# LMP2011basedV2.net
KiCad netlist of a schematic drawn in EAGLE
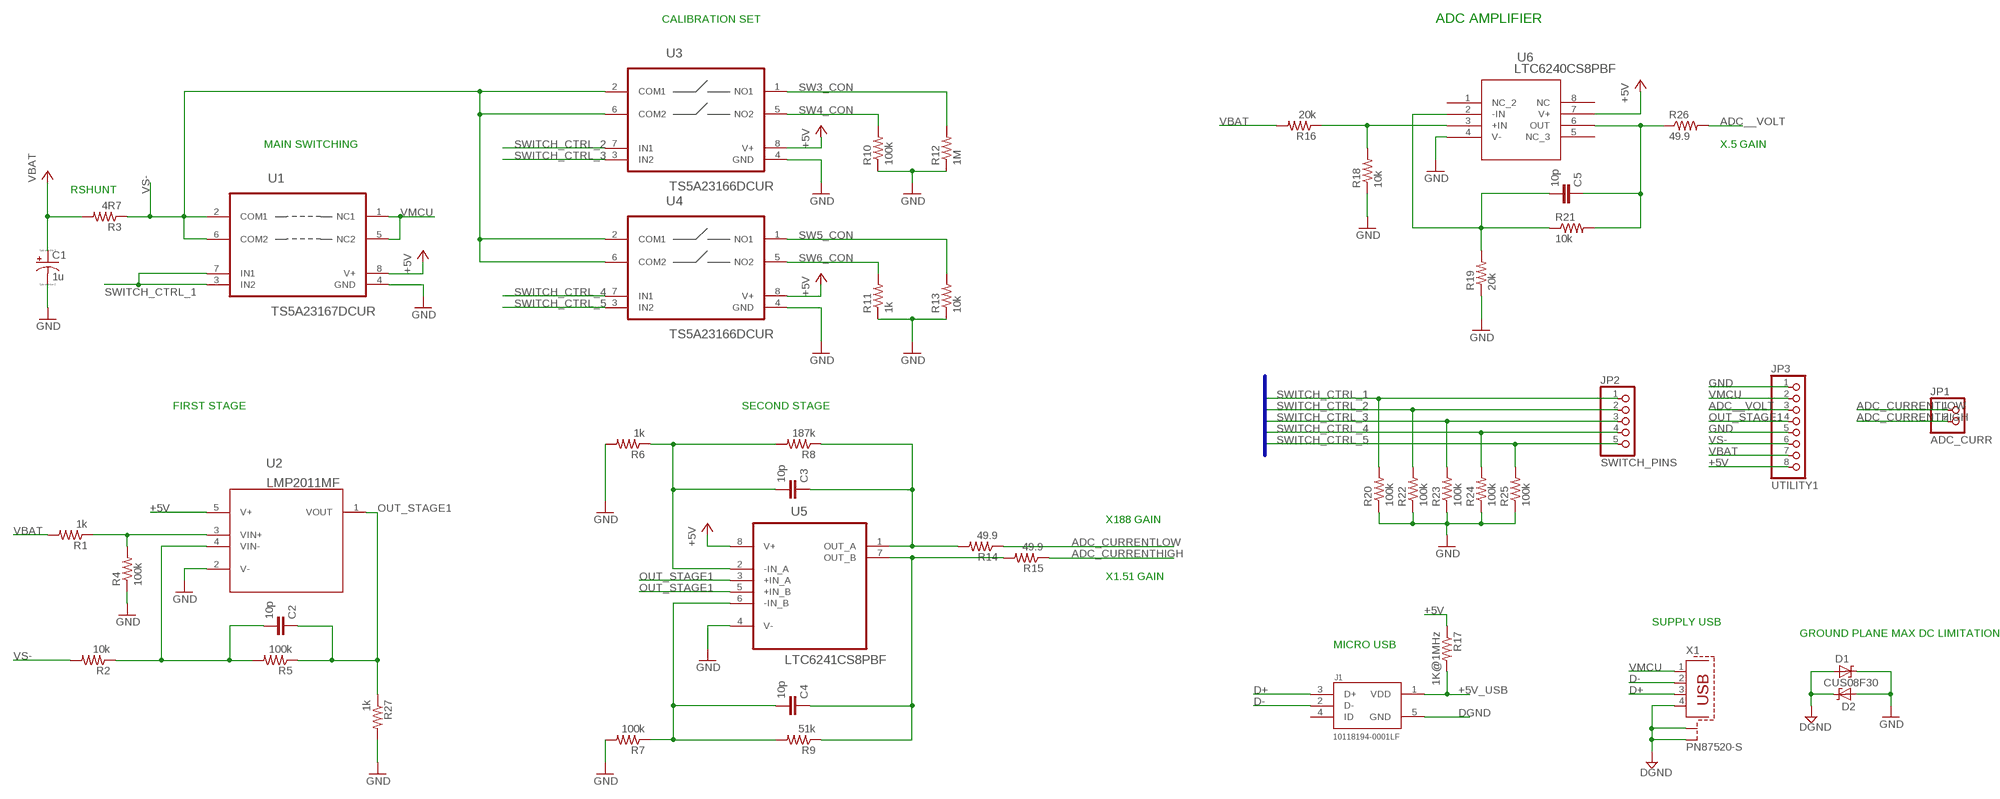
[diagram p0: schematic, sheet 1]

(export (version "E")
  (design (tool "Eeschema 10.0.6"))
  (components
    (comp (ref "C1")
      (value "1u")
      (footprint "eagle-import:PANASONIC_B")
      (libsource (lib "eagle-import") (part "CPOL-USB"))
    )
    (comp (ref "C2")
      (value "10p")
      (footprint "eagle-import:C0805")
      (libsource (lib "eagle-import") (part "C-EUC0805"))
    )
    (comp (ref "C3")
      (value "10p")
      (footprint "eagle-import:C0805")
      (libsource (lib "eagle-import") (part "C-EUC0805"))
    )
    (comp (ref "C4")
      (value "10p")
      (footprint "eagle-import:C0805")
      (libsource (lib "eagle-import") (part "C-EUC0805"))
    )
    (comp (ref "C5")
      (value "10p")
      (footprint "eagle-import:C0805")
      (libsource (lib "eagle-import") (part "C-EUC0805"))
    )
    (comp (ref "D1")
      (value "CUS08F30")
      (footprint "eagle-import:SOD323")
      (fields (field (name "MF") "TOSHIBA"))
      (libsource (lib "eagle-import") (part "CUS08F30"))
    )
    (comp (ref "D2")
      (value "CUS08F30")
      (footprint "eagle-import:SOD323")
      (fields (field (name "MF") "TOSHIBA"))
      (libsource (lib "eagle-import") (part "CUS08F30"))
    )
    (comp (ref "J1")
      (value "10118194-0001LF")
      (footprint "eagle-import:FRAMATOME_10118194-0001LF")
      (fields (field (name "MF") "Amphenol"))
      (libsource (lib "eagle-import") (part "10118194-0001LF"))
    )
    (comp (ref "JP1")
      (value "ADC_CURR")
      (footprint "eagle-import:1X02")
      (libsource (lib "eagle-import") (part "PINHD-1X2"))
    )
    (comp (ref "JP2")
      (value "SWITCH_PINS")
      (footprint "eagle-import:1X05")
      (libsource (lib "eagle-import") (part "PINHD-1X5"))
    )
    (comp (ref "JP3")
      (value "UTILITY1")
      (footprint "eagle-import:1X08")
      (libsource (lib "eagle-import") (part "PINHD-1X8"))
    )
    (comp (ref "R1")
      (value "1k")
      (footprint "eagle-import:R0805")
      (libsource (lib "eagle-import") (part "R-US_R0805"))
    )
    (comp (ref "R2")
      (value "10k")
      (footprint "eagle-import:R0805")
      (libsource (lib "eagle-import") (part "R-US_R0805"))
    )
    (comp (ref "R3")
      (value "4R7")
      (footprint "eagle-import:R0805")
      (libsource (lib "eagle-import") (part "R-US_R0805"))
    )
    (comp (ref "R4")
      (value "100k")
      (footprint "eagle-import:R0805")
      (libsource (lib "eagle-import") (part "R-US_R0805"))
    )
    (comp (ref "R5")
      (value "100k")
      (footprint "eagle-import:R0805")
      (libsource (lib "eagle-import") (part "R-US_R0805"))
    )
    (comp (ref "R6")
      (value "1k")
      (footprint "eagle-import:R0805")
      (libsource (lib "eagle-import") (part "R-US_R0805"))
    )
    (comp (ref "R7")
      (value "100k")
      (footprint "eagle-import:R0805")
      (libsource (lib "eagle-import") (part "R-US_R0805"))
    )
    (comp (ref "R8")
      (value "187k")
      (footprint "eagle-import:R0805")
      (libsource (lib "eagle-import") (part "R-US_R0805"))
    )
    (comp (ref "R9")
      (value "51k")
      (footprint "eagle-import:R0805")
      (libsource (lib "eagle-import") (part "R-US_R0805"))
    )
    (comp (ref "R10")
      (value "100k")
      (footprint "eagle-import:R0805")
      (libsource (lib "eagle-import") (part "R-US_R0805"))
    )
    (comp (ref "R11")
      (value "1k")
      (footprint "eagle-import:R0805")
      (libsource (lib "eagle-import") (part "R-US_R0805"))
    )
    (comp (ref "R12")
      (value "1M")
      (footprint "eagle-import:R0805")
      (libsource (lib "eagle-import") (part "R-US_R0805"))
    )
    (comp (ref "R13")
      (value "10k")
      (footprint "eagle-import:R0805")
      (libsource (lib "eagle-import") (part "R-US_R0805"))
    )
    (comp (ref "R14")
      (value "49.9")
      (footprint "eagle-import:R0805")
      (libsource (lib "eagle-import") (part "R-US_R0805"))
    )
    (comp (ref "R15")
      (value "49.9")
      (footprint "eagle-import:R0805")
      (libsource (lib "eagle-import") (part "R-US_R0805"))
    )
    (comp (ref "R16")
      (value "20k")
      (footprint "eagle-import:R0805")
      (libsource (lib "eagle-import") (part "R-US_R0805"))
    )
    (comp (ref "R17")
      (value "1K@1MHz")
      (footprint "eagle-import:R0805")
      (libsource (lib "eagle-import") (part "R-US_R0805"))
    )
    (comp (ref "R18")
      (value "10k")
      (footprint "eagle-import:R0805")
      (libsource (lib "eagle-import") (part "R-US_R0805"))
    )
    (comp (ref "R19")
      (value "20k")
      (footprint "eagle-import:R0805")
      (libsource (lib "eagle-import") (part "R-US_R0805"))
    )
    (comp (ref "R20")
      (value "100k")
      (footprint "eagle-import:R0805")
      (libsource (lib "eagle-import") (part "R-US_R0805"))
    )
    (comp (ref "R21")
      (value "10k")
      (footprint "eagle-import:R0805")
      (libsource (lib "eagle-import") (part "R-US_R0805"))
    )
    (comp (ref "R22")
      (value "100k")
      (footprint "eagle-import:R0805")
      (libsource (lib "eagle-import") (part "R-US_R0805"))
    )
    (comp (ref "R23")
      (value "100k")
      (footprint "eagle-import:R0805")
      (libsource (lib "eagle-import") (part "R-US_R0805"))
    )
    (comp (ref "R24")
      (value "100k")
      (footprint "eagle-import:R0805")
      (libsource (lib "eagle-import") (part "R-US_R0805"))
    )
    (comp (ref "R25")
      (value "100k")
      (footprint "eagle-import:R0805")
      (libsource (lib "eagle-import") (part "R-US_R0805"))
    )
    (comp (ref "R26")
      (value "49.9")
      (footprint "eagle-import:R0603")
      (libsource (lib "eagle-import") (part "R-US_R0603"))
    )
    (comp (ref "R27")
      (value "1k")
      (footprint "eagle-import:R0805")
      (libsource (lib "eagle-import") (part "R-US_R0805"))
    )
    (comp (ref "U1")
      (value "TS5A23167DCUR")
      (footprint "eagle-import:SOP50P310X90-8N")
      (fields (field (name "MF") "Texas Instruments"))
      (libsource (lib "eagle-import") (part "TS5A23167DCUR"))
    )
    (comp (ref "U2")
      (value "LMP2011MF")
      (footprint "eagle-import:SOT95P285X120-5N")
      (fields
        (field (name "DIGI-KEY_PART_NUMBER") "LMP2011MF/NOPBCT-ND")
        (field (name "MF") "Texas Instruments")
        (field (name "MP") "LMP2011MF/NOPB")
      )
      (libsource (lib "eagle-import") (part "LMP2011MF"))
    )
    (comp (ref "U3")
      (value "TS5A23166DCUR")
      (footprint "eagle-import:SOP50P310X90-8N")
      (fields (field (name "MF") "Texas Instruments"))
      (libsource (lib "eagle-import") (part "TS5A23166DCUR"))
    )
    (comp (ref "U4")
      (value "TS5A23166DCUR")
      (footprint "eagle-import:SOP50P310X90-8N")
      (fields (field (name "MF") "Texas Instruments"))
      (libsource (lib "eagle-import") (part "TS5A23166DCUR"))
    )
    (comp (ref "U5")
      (value "LTC6241CS8PBF")
      (footprint "eagle-import:SOIC127P600X175-8N")
      (fields (field (name "MF") "Linear Technology") (field (name "MP") "LTC6241CS8#PBF"))
      (libsource (lib "eagle-import") (part "LTC6241CS8PBF"))
    )
    (comp (ref "U6")
      (value "LTC6240CS8PBF")
      (footprint "eagle-import:SO-8_S")
      (fields (field (name "MF") "Linear Technology") (field (name "MP") "LTC6240CS8#PBF"))
      (libsource (lib "eagle-import") (part "LTC6240CS8PBF"))
    )
    (comp (ref "X1")
      (value "PN87520-S")
      (footprint "eagle-import:PN87520-S")
      (libsource (lib "eagle-import") (part "PN87520-S"))
    )
  )
  (nets
    (net (code "1") (name "+5V") (class "Default")
      (node (ref "JP3") (pin "8") (pinfunction "8_8") (pintype "passive"))
      (node (ref "R17") (pin "1") (pinfunction "1_1") (pintype "passive"))
      (node (ref "U1") (pin "8") (pinfunction "V+_8") (pintype "power_in"))
      (node (ref "U2") (pin "5") (pinfunction "V+_5") (pintype "power_in"))
      (node (ref "U3") (pin "8") (pinfunction "V+_8") (pintype "power_in"))
      (node (ref "U4") (pin "8") (pinfunction "V+_8") (pintype "power_in"))
      (node (ref "U5") (pin "8") (pinfunction "V+_8") (pintype "power_in"))
      (node (ref "U6") (pin "7") (pinfunction "V+_7") (pintype "power_in"))
    )
    (net (code "2") (name "/+5V_USB") (class "Default")
      (node (ref "J1") (pin "1") (pinfunction "VDD_1") (pintype "power_in"))
      (node (ref "R17") (pin "2") (pinfunction "2_2") (pintype "passive"))
    )
    (net (code "3") (name "/ADC_CURRENTHIGH") (class "Default")
      (node (ref "JP1") (pin "2") (pinfunction "2_2") (pintype "passive"))
      (node (ref "R15") (pin "1") (pinfunction "1_1") (pintype "passive"))
    )
    (net (code "4") (name "/ADC_CURRENTLOW") (class "Default")
      (node (ref "JP1") (pin "1") (pinfunction "1_1") (pintype "passive"))
      (node (ref "R14") (pin "1") (pinfunction "1_1") (pintype "passive"))
    )
    (net (code "5") (name "/ADC__VOLT") (class "Default")
      (node (ref "JP3") (pin "3") (pinfunction "3_3") (pintype "passive"))
      (node (ref "R26") (pin "2") (pinfunction "2_2") (pintype "passive"))
    )
    (net (code "6") (name "/D+") (class "Default")
      (node (ref "J1") (pin "3") (pinfunction "D+_3") (pintype "bidirectional"))
      (node (ref "X1") (pin "3") (pinfunction "3_3") (pintype "passive"))
    )
    (net (code "7") (name "/D-") (class "Default")
      (node (ref "J1") (pin "2") (pinfunction "D-_2") (pintype "bidirectional"))
      (node (ref "X1") (pin "2") (pinfunction "2_2") (pintype "passive"))
    )
    (net (code "8") (name "/OUT_STAGE1") (class "Default")
      (node (ref "C2") (pin "1") (pinfunction "1_1") (pintype "passive"))
      (node (ref "JP3") (pin "4") (pinfunction "4_4") (pintype "passive"))
      (node (ref "R27") (pin "1") (pinfunction "1_1") (pintype "passive"))
      (node (ref "R5") (pin "1") (pinfunction "1_1") (pintype "passive"))
      (node (ref "U2") (pin "1") (pinfunction "VOUT_1") (pintype "output"))
      (node (ref "U5") (pin "3") (pinfunction "+IN_A_3") (pintype "input"))
      (node (ref "U5") (pin "5") (pinfunction "+IN_B_5") (pintype "input"))
    )
    (net (code "9") (name "/SW3_CON") (class "Default")
      (node (ref "R12") (pin "2") (pinfunction "2_2") (pintype "passive"))
      (node (ref "U3") (pin "1") (pinfunction "NO1_1") (pintype "bidirectional"))
    )
    (net (code "10") (name "/SW4_CON") (class "Default")
      (node (ref "R10") (pin "2") (pinfunction "2_2") (pintype "passive"))
      (node (ref "U3") (pin "5") (pinfunction "NO2_5") (pintype "bidirectional"))
    )
    (net (code "11") (name "/SW5_CON") (class "Default")
      (node (ref "R13") (pin "2") (pinfunction "2_2") (pintype "passive"))
      (node (ref "U4") (pin "1") (pinfunction "NO1_1") (pintype "bidirectional"))
    )
    (net (code "12") (name "/SW6_CON") (class "Default")
      (node (ref "R11") (pin "2") (pinfunction "2_2") (pintype "passive"))
      (node (ref "U4") (pin "5") (pinfunction "NO2_5") (pintype "bidirectional"))
    )
    (net (code "13") (name "/SWITCH_CTRL_1") (class "Default")
      (node (ref "JP2") (pin "1") (pinfunction "1_1") (pintype "passive"))
      (node (ref "R20") (pin "2") (pinfunction "2_2") (pintype "passive"))
      (node (ref "U1") (pin "3") (pinfunction "IN2_3") (pintype "input"))
      (node (ref "U1") (pin "7") (pinfunction "IN1_7") (pintype "input"))
    )
    (net (code "14") (name "/SWITCH_CTRL_2") (class "Default")
      (node (ref "JP2") (pin "2") (pinfunction "2_2") (pintype "passive"))
      (node (ref "R22") (pin "2") (pinfunction "2_2") (pintype "passive"))
      (node (ref "U3") (pin "7") (pinfunction "IN1_7") (pintype "input"))
    )
    (net (code "15") (name "/SWITCH_CTRL_3") (class "Default")
      (node (ref "JP2") (pin "3") (pinfunction "3_3") (pintype "passive"))
      (node (ref "R23") (pin "2") (pinfunction "2_2") (pintype "passive"))
      (node (ref "U3") (pin "3") (pinfunction "IN2_3") (pintype "input"))
    )
    (net (code "16") (name "/SWITCH_CTRL_4") (class "Default")
      (node (ref "JP2") (pin "4") (pinfunction "4_4") (pintype "passive"))
      (node (ref "R24") (pin "2") (pinfunction "2_2") (pintype "passive"))
      (node (ref "U4") (pin "7") (pinfunction "IN1_7") (pintype "input"))
    )
    (net (code "17") (name "/SWITCH_CTRL_5") (class "Default")
      (node (ref "JP2") (pin "5") (pinfunction "5_5") (pintype "passive"))
      (node (ref "R25") (pin "2") (pinfunction "2_2") (pintype "passive"))
      (node (ref "U4") (pin "3") (pinfunction "IN2_3") (pintype "input"))
    )
    (net (code "18") (name "/VMCU") (class "Default")
      (node (ref "JP3") (pin "2") (pinfunction "2_2") (pintype "passive"))
      (node (ref "U1") (pin "1") (pinfunction "NC1_1") (pintype "bidirectional"))
      (node (ref "U1") (pin "5") (pinfunction "NC2_5") (pintype "bidirectional"))
      (node (ref "X1") (pin "1") (pinfunction "1_1") (pintype "passive"))
    )
    (net (code "19") (name "/VS-") (class "Default")
      (node (ref "JP3") (pin "6") (pinfunction "6_6") (pintype "passive"))
      (node (ref "R2") (pin "2") (pinfunction "2_2") (pintype "passive"))
      (node (ref "R3") (pin "1") (pinfunction "1_1") (pintype "passive"))
      (node (ref "U1") (pin "2") (pinfunction "COM1_2") (pintype "bidirectional"))
      (node (ref "U1") (pin "6") (pinfunction "COM2_6") (pintype "bidirectional"))
      (node (ref "U3") (pin "2") (pinfunction "COM1_2") (pintype "bidirectional"))
      (node (ref "U3") (pin "6") (pinfunction "COM2_6") (pintype "bidirectional"))
      (node (ref "U4") (pin "2") (pinfunction "COM1_2") (pintype "bidirectional"))
      (node (ref "U4") (pin "6") (pinfunction "COM2_6") (pintype "bidirectional"))
    )
    (net (code "20") (name "DGND") (class "Default")
      (node (ref "D1") (pin "A") (pinfunction "A_A") (pintype "passive"))
      (node (ref "D2") (pin "C") (pinfunction "C_C") (pintype "passive"))
      (node (ref "J1") (pin "5") (pinfunction "GND_5") (pintype "power_in"))
      (node (ref "X1") (pin "4") (pinfunction "4_4") (pintype "passive"))
      (node (ref "X1") (pin "S1") (pinfunction "S1_S1") (pintype "passive"))
      (node (ref "X1") (pin "S2") (pinfunction "S2_S2") (pintype "passive"))
    )
    (net (code "21") (name "GND") (class "Default")
      (node (ref "C1") (pin "-") (pinfunction "-_-") (pintype "passive"))
      (node (ref "D1") (pin "C") (pinfunction "C_C") (pintype "passive"))
      (node (ref "D2") (pin "A") (pinfunction "A_A") (pintype "passive"))
      (node (ref "JP3") (pin "1") (pinfunction "1_1") (pintype "passive"))
      (node (ref "JP3") (pin "5") (pinfunction "5_5") (pintype "passive"))
      (node (ref "R10") (pin "1") (pinfunction "1_1") (pintype "passive"))
      (node (ref "R11") (pin "1") (pinfunction "1_1") (pintype "passive"))
      (node (ref "R12") (pin "1") (pinfunction "1_1") (pintype "passive"))
      (node (ref "R13") (pin "1") (pinfunction "1_1") (pintype "passive"))
      (node (ref "R18") (pin "1") (pinfunction "1_1") (pintype "passive"))
      (node (ref "R19") (pin "1") (pinfunction "1_1") (pintype "passive"))
      (node (ref "R20") (pin "1") (pinfunction "1_1") (pintype "passive"))
      (node (ref "R22") (pin "1") (pinfunction "1_1") (pintype "passive"))
      (node (ref "R23") (pin "1") (pinfunction "1_1") (pintype "passive"))
      (node (ref "R24") (pin "1") (pinfunction "1_1") (pintype "passive"))
      (node (ref "R25") (pin "1") (pinfunction "1_1") (pintype "passive"))
      (node (ref "R27") (pin "2") (pinfunction "2_2") (pintype "passive"))
      (node (ref "R4") (pin "1") (pinfunction "1_1") (pintype "passive"))
      (node (ref "R6") (pin "2") (pinfunction "2_2") (pintype "passive"))
      (node (ref "R7") (pin "2") (pinfunction "2_2") (pintype "passive"))
      (node (ref "U1") (pin "4") (pinfunction "GND_4") (pintype "passive"))
      (node (ref "U2") (pin "2") (pinfunction "V-_2") (pintype "power_in"))
      (node (ref "U3") (pin "4") (pinfunction "GND_4") (pintype "passive"))
      (node (ref "U4") (pin "4") (pinfunction "GND_4") (pintype "passive"))
      (node (ref "U5") (pin "4") (pinfunction "V-_4") (pintype "power_in"))
      (node (ref "U6") (pin "4") (pinfunction "V-_4") (pintype "power_in"))
    )
    (net (code "22") (name "Net-(U2-VIN+)") (class "Default")
      (node (ref "R1") (pin "1") (pinfunction "1_1") (pintype "passive"))
      (node (ref "R4") (pin "2") (pinfunction "2_2") (pintype "passive"))
      (node (ref "U2") (pin "3") (pinfunction "VIN+_3") (pintype "input"))
    )
    (net (code "23") (name "Net-(U2-VIN-)") (class "Default")
      (node (ref "C2") (pin "2") (pinfunction "2_2") (pintype "passive"))
      (node (ref "R2") (pin "1") (pinfunction "1_1") (pintype "passive"))
      (node (ref "R5") (pin "2") (pinfunction "2_2") (pintype "passive"))
      (node (ref "U2") (pin "4") (pinfunction "VIN-_4") (pintype "input"))
    )
    (net (code "24") (name "Net-(U5--IN_A)") (class "Default")
      (node (ref "C3") (pin "2") (pinfunction "2_2") (pintype "passive"))
      (node (ref "R6") (pin "1") (pinfunction "1_1") (pintype "passive"))
      (node (ref "R8") (pin "2") (pinfunction "2_2") (pintype "passive"))
      (node (ref "U5") (pin "2") (pinfunction "-IN_A_2") (pintype "input"))
    )
    (net (code "25") (name "Net-(U5--IN_B)") (class "Default")
      (node (ref "C4") (pin "2") (pinfunction "2_2") (pintype "passive"))
      (node (ref "R7") (pin "1") (pinfunction "1_1") (pintype "passive"))
      (node (ref "R9") (pin "2") (pinfunction "2_2") (pintype "passive"))
      (node (ref "U5") (pin "6") (pinfunction "-IN_B_6") (pintype "input"))
    )
    (net (code "26") (name "Net-(U5-OUT_A)") (class "Default")
      (node (ref "C3") (pin "1") (pinfunction "1_1") (pintype "passive"))
      (node (ref "R14") (pin "2") (pinfunction "2_2") (pintype "passive"))
      (node (ref "R8") (pin "1") (pinfunction "1_1") (pintype "passive"))
      (node (ref "U5") (pin "1") (pinfunction "OUT_A_1") (pintype "output"))
    )
    (net (code "27") (name "Net-(U5-OUT_B)") (class "Default")
      (node (ref "C4") (pin "1") (pinfunction "1_1") (pintype "passive"))
      (node (ref "R15") (pin "2") (pinfunction "2_2") (pintype "passive"))
      (node (ref "R9") (pin "1") (pinfunction "1_1") (pintype "passive"))
      (node (ref "U5") (pin "7") (pinfunction "OUT_B_7") (pintype "output"))
    )
    (net (code "28") (name "Net-(U6-+IN)") (class "Default")
      (node (ref "R16") (pin "1") (pinfunction "1_1") (pintype "passive"))
      (node (ref "R18") (pin "2") (pinfunction "2_2") (pintype "passive"))
      (node (ref "U6") (pin "3") (pinfunction "+IN_3") (pintype "input"))
    )
    (net (code "29") (name "Net-(U6--IN)") (class "Default")
      (node (ref "C5") (pin "2") (pinfunction "2_2") (pintype "passive"))
      (node (ref "R19") (pin "2") (pinfunction "2_2") (pintype "passive"))
      (node (ref "R21") (pin "1") (pinfunction "1_1") (pintype "passive"))
      (node (ref "U6") (pin "2") (pinfunction "-IN_2") (pintype "input"))
    )
    (net (code "30") (name "Net-(U6-OUT)") (class "Default")
      (node (ref "C5") (pin "1") (pinfunction "1_1") (pintype "passive"))
      (node (ref "R21") (pin "2") (pinfunction "2_2") (pintype "passive"))
      (node (ref "R26") (pin "1") (pinfunction "1_1") (pintype "passive"))
      (node (ref "U6") (pin "6") (pinfunction "OUT_6") (pintype "output"))
    )
    (net (code "31") (name "VBAT") (class "Default")
      (node (ref "C1") (pin "+") (pinfunction "+_+") (pintype "passive"))
      (node (ref "JP3") (pin "7") (pinfunction "7_7") (pintype "passive"))
      (node (ref "R1") (pin "2") (pinfunction "2_2") (pintype "passive"))
      (node (ref "R16") (pin "2") (pinfunction "2_2") (pintype "passive"))
      (node (ref "R3") (pin "2") (pinfunction "2_2") (pintype "passive"))
    )
    (net (code "32") (name "unconnected-(J1-ID-Pad4)") (class "Default")
      (node (ref "J1") (pin "4") (pinfunction "ID_4") (pintype "passive"))
    )
    (net (code "33") (name "unconnected-(U6-NC-Pad8)") (class "Default")
      (node (ref "U6") (pin "8") (pinfunction "NC_8") (pintype "no_connect"))
    )
    (net (code "34") (name "unconnected-(U6-NC_2-Pad1)") (class "Default")
      (node (ref "U6") (pin "1") (pinfunction "NC_2_1") (pintype "no_connect"))
    )
    (net (code "35") (name "unconnected-(U6-NC_3-Pad5)") (class "Default")
      (node (ref "U6") (pin "5") (pinfunction "NC_3_5") (pintype "no_connect"))
    )
  )
)
